# SwitchBoard_v4.net
KiCad netlist of a schematic drawn in Altium Designer
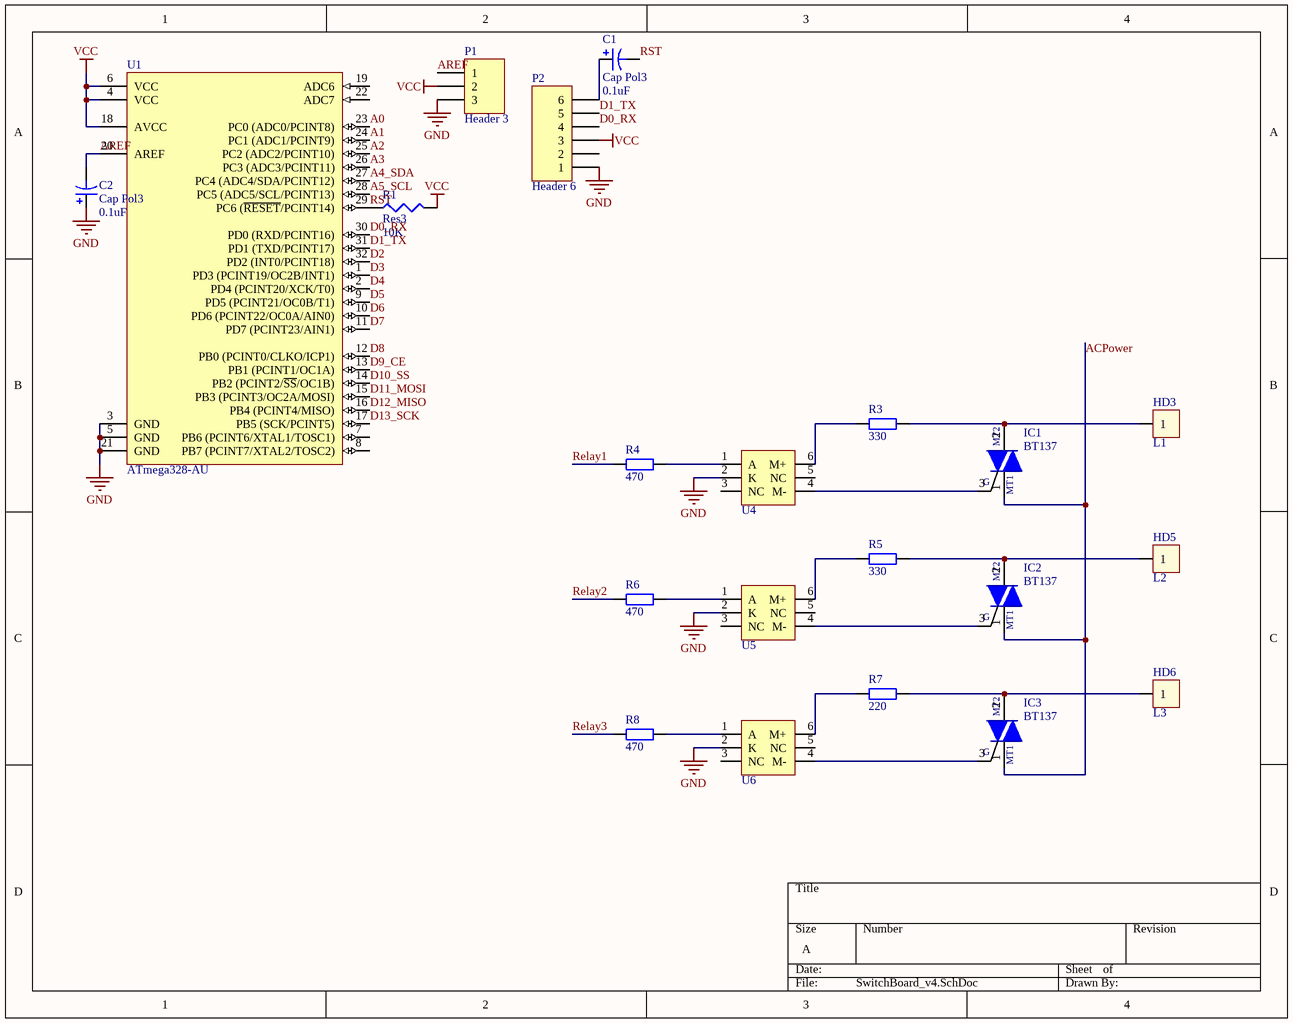
[diagram p0: SwitchBoard_v4.SchDoc]

(export (version "E")
  (design (tool "Eeschema 10.0.6"))
  (components
    (comp (ref "C1")
      (value "Cap Pol3")
      (footprint "C0805")
      (description "Polarized Capacitor (Surface Mount)")
      (fields (field (name "ALTIUM_VALUE") "0.1uF") (field (name "PUBLISHER") "Altium Limited"))
      (libsource (lib "Miscellaneous Devices") (part "Cap Pol3"))
    )
    (comp (ref "C2")
      (value "Cap Pol3")
      (footprint "C0805")
      (description "Polarized Capacitor (Surface Mount)")
      (fields (field (name "ALTIUM_VALUE") "0.1uF") (field (name "PUBLISHER") "Altium Limited"))
      (libsource (lib "Miscellaneous Devices") (part "Cap Pol3"))
    )
    (comp (ref "HD3")
      (value "L1")
      (footprint "DOMINO1")
      (description "Header 2 (Green)")
      (libsource (lib "myLibs") (part "Domino1"))
    )
    (comp (ref "HD5")
      (value "L2")
      (footprint "DOMINO1")
      (description "Header 2 (Green)")
      (libsource (lib "myLibs") (part "Domino1"))
    )
    (comp (ref "HD6")
      (value "L3")
      (footprint "DOMINO1")
      (description "Header 2 (Green)")
      (libsource (lib "myLibs") (part "Domino1"))
    )
    (comp (ref "IC1")
      (value "BT137")
      (footprint "QTO-220")
      (description "Triacs - 8A")
      (libsource (lib "myLibs") (part "BT137"))
    )
    (comp (ref "IC2")
      (value "BT137")
      (footprint "QTO-220")
      (description "Triacs - 8A")
      (libsource (lib "myLibs") (part "BT137"))
    )
    (comp (ref "IC3")
      (value "BT137")
      (footprint "QTO-220")
      (description "Triacs - 8A")
      (libsource (lib "myLibs") (part "BT137"))
    )
    (comp (ref "P1")
      (value "Header 3")
      (footprint "HDR1X3")
      (description "Header, 3-Pin")
      (fields (field (name "PUBLISHER") "Altium Limited"))
      (libsource (lib "Miscellaneous Connectors") (part "Header 3"))
    )
    (comp (ref "P2")
      (value "Header 6")
      (footprint "HDR1X6")
      (description "Header, 6-Pin")
      (fields (field (name "PUBLISHER") "Altium Limited"))
      (libsource (lib "Miscellaneous Connectors") (part "Header 6"))
    )
    (comp (ref "R1")
      (value "Res3")
      (footprint "J1-0603")
      (description "Resistor")
      (fields (field (name "ALTIUM_VALUE") "10K") (field (name "PUBLISHER") "Altium Limited"))
      (libsource (lib "Miscellaneous Devices") (part "Res3"))
    )
    (comp (ref "R3")
      (value "330")
      (footprint "R1/4W")
      (description "Resistor 1/4W")
      (libsource (lib "myLibs") (part "R1/4W"))
    )
    (comp (ref "R4")
      (value "470")
      (footprint "R1/4W")
      (description "Resistor 1/4W")
      (libsource (lib "myLibs") (part "R1/4W"))
    )
    (comp (ref "R5")
      (value "330")
      (footprint "R1/4W")
      (description "Resistor 1/4W")
      (libsource (lib "myLibs") (part "R1/4W"))
    )
    (comp (ref "R6")
      (value "470")
      (footprint "R1/4W")
      (description "Resistor 1/4W")
      (libsource (lib "myLibs") (part "R1/4W"))
    )
    (comp (ref "R7")
      (value "220")
      (footprint "R1/4W")
      (description "Resistor 1/4W")
      (libsource (lib "myLibs") (part "R1/4W"))
    )
    (comp (ref "R8")
      (value "470")
      (footprint "R1/4W")
      (description "Resistor 1/4W")
      (libsource (lib "myLibs") (part "R1/4W"))
    )
    (comp (ref "U1")
      (value "ATmega328-AU")
      (footprint "32A_N")
      (fields (field (name "PUBLISHER") "Altium Limited"))
      (libsource (lib "Atmel Microcontroller 8-Bit megaAVR") (part "ATmega328-AU"))
    )
    (comp (ref "U4") (value "MOC3021M") (footprint "MOC30XX") (libsource (lib "myLibs") (part "MOC3021M")))
    (comp (ref "U5") (value "MOC3021M") (footprint "MOC30XX") (libsource (lib "myLibs") (part "MOC3021M")))
    (comp (ref "U6") (value "MOC3021M") (footprint "MOC30XX") (libsource (lib "myLibs") (part "MOC3021M")))
  )
  (nets
    (net (code "1") (name "/A0") (class "Default")
      (node (ref "U1") (pin "23") (pinfunction "PC0_(ADC0/PCINT8)_23") (pintype "bidirectional"))
    )
    (net (code "2") (name "/A1") (class "Default")
      (node (ref "U1") (pin "24") (pinfunction "PC1_(ADC1/PCINT9)_24") (pintype "bidirectional"))
    )
    (net (code "3") (name "/A2") (class "Default")
      (node (ref "U1") (pin "25") (pinfunction "PC2_(ADC2/PCINT10)_25") (pintype "bidirectional"))
    )
    (net (code "4") (name "/A3") (class "Default")
      (node (ref "U1") (pin "26") (pinfunction "PC3_(ADC3/PCINT11)_26") (pintype "bidirectional"))
    )
    (net (code "5") (name "/A4_SDA") (class "Default")
      (node (ref "U1") (pin "27") (pinfunction "PC4_(ADC4/SDA/PCINT12)_27") (pintype "bidirectional"))
    )
    (net (code "6") (name "/A5_SCL") (class "Default")
      (node (ref "U1") (pin "28") (pinfunction "PC5_(ADC5/SCL/PCINT13)_28") (pintype "bidirectional"))
    )
    (net (code "7") (name "/ACPower") (class "Default")
      (node (ref "IC1") (pin "1") (pinfunction "MT1_1") (pintype "passive"))
      (node (ref "IC2") (pin "1") (pinfunction "MT1_1") (pintype "passive"))
      (node (ref "IC3") (pin "1") (pinfunction "MT1_1") (pintype "passive"))
    )
    (net (code "8") (name "/AREF") (class "Default")
      (node (ref "C2") (pin "2") (pinfunction "2_2") (pintype "passive"))
      (node (ref "P1") (pin "1") (pinfunction "1_1") (pintype "passive"))
      (node (ref "U1") (pin "20") (pinfunction "AREF_20") (pintype "passive"))
    )
    (net (code "9") (name "/D0_RX") (class "Default")
      (node (ref "P2") (pin "4") (pinfunction "4_4") (pintype "passive"))
      (node (ref "U1") (pin "30") (pinfunction "PD0_(RXD/PCINT16)_30") (pintype "bidirectional"))
    )
    (net (code "10") (name "/D1_TX") (class "Default")
      (node (ref "P2") (pin "5") (pinfunction "5_5") (pintype "passive"))
      (node (ref "U1") (pin "31") (pinfunction "PD1_(TXD/PCINT17)_31") (pintype "bidirectional"))
    )
    (net (code "11") (name "/D2") (class "Default")
      (node (ref "U1") (pin "32") (pinfunction "PD2_(INT0/PCINT18)_32") (pintype "bidirectional"))
    )
    (net (code "12") (name "/D3") (class "Default")
      (node (ref "U1") (pin "1") (pinfunction "PD3_(PCINT19/OC2B/INT1)_1") (pintype "bidirectional"))
    )
    (net (code "13") (name "/D4") (class "Default")
      (node (ref "U1") (pin "2") (pinfunction "PD4_(PCINT20/XCK/T0)_2") (pintype "bidirectional"))
    )
    (net (code "14") (name "/D5") (class "Default")
      (node (ref "U1") (pin "9") (pinfunction "PD5_(PCINT21/OC0B/T1)_9") (pintype "bidirectional"))
    )
    (net (code "15") (name "/D6") (class "Default")
      (node (ref "U1") (pin "10") (pinfunction "PD6_(PCINT22/OC0A/AIN0)_10") (pintype "bidirectional"))
    )
    (net (code "16") (name "/D7") (class "Default")
      (node (ref "U1") (pin "11") (pinfunction "PD7_(PCINT23/AIN1)_11") (pintype "bidirectional"))
    )
    (net (code "17") (name "/D8") (class "Default")
      (node (ref "U1") (pin "12") (pinfunction "PB0_(PCINT0/CLKO/ICP1)_12") (pintype "bidirectional"))
    )
    (net (code "18") (name "/D9_CE") (class "Default")
      (node (ref "U1") (pin "13") (pinfunction "PB1_(PCINT1/OC1A)_13") (pintype "bidirectional"))
    )
    (net (code "19") (name "/D10_SS") (class "Default")
      (node (ref "U1") (pin "14") (pinfunction "PB2_(PCINT2/~{SS}/OC1B)_14") (pintype "bidirectional"))
    )
    (net (code "20") (name "/D11_MOSI") (class "Default")
      (node (ref "U1") (pin "15") (pinfunction "PB3_(PCINT3/OC2A/MOSI)_15") (pintype "bidirectional"))
    )
    (net (code "21") (name "/D12_MISO") (class "Default")
      (node (ref "U1") (pin "16") (pinfunction "PB4_(PCINT4/MISO)_16") (pintype "bidirectional"))
    )
    (net (code "22") (name "/D13_SCK") (class "Default")
      (node (ref "U1") (pin "17") (pinfunction "PB5_(SCK/PCINT5)_17") (pintype "bidirectional"))
    )
    (net (code "23") (name "/RST") (class "Default")
      (node (ref "C1") (pin "2") (pinfunction "2_2") (pintype "passive"))
      (node (ref "R1") (pin "1") (pinfunction "1_1") (pintype "passive"))
      (node (ref "U1") (pin "29") (pinfunction "PC6_(~{RESET}/PCINT14)_29") (pintype "bidirectional"))
    )
    (net (code "24") (name "/Relay1") (class "Default")
      (node (ref "R4") (pin "1") (pinfunction "1_1") (pintype "passive"))
    )
    (net (code "25") (name "/Relay2") (class "Default")
      (node (ref "R6") (pin "1") (pinfunction "1_1") (pintype "passive"))
    )
    (net (code "26") (name "/Relay3") (class "Default")
      (node (ref "R8") (pin "1") (pinfunction "1_1") (pintype "passive"))
    )
    (net (code "27") (name "GND") (class "Default")
      (node (ref "C2") (pin "1") (pinfunction "1_1") (pintype "passive"))
      (node (ref "P1") (pin "3") (pinfunction "3_3") (pintype "passive"))
      (node (ref "P2") (pin "1") (pinfunction "1_1") (pintype "passive"))
      (node (ref "U1") (pin "21") (pinfunction "GND_21") (pintype "power_in"))
      (node (ref "U1") (pin "3") (pinfunction "GND_3") (pintype "power_in"))
      (node (ref "U1") (pin "5") (pinfunction "GND_5") (pintype "power_in"))
      (node (ref "U4") (pin "2") (pinfunction "K_2") (pintype "passive"))
      (node (ref "U5") (pin "2") (pinfunction "K_2") (pintype "passive"))
      (node (ref "U6") (pin "2") (pinfunction "K_2") (pintype "passive"))
    )
    (net (code "28") (name "Net-(C1-Pad1)") (class "Default")
      (node (ref "C1") (pin "1") (pinfunction "1_1") (pintype "passive"))
      (node (ref "P2") (pin "6") (pinfunction "6_6") (pintype "passive"))
    )
    (net (code "29") (name "Net-(IC1-IN)") (class "Default")
      (node (ref "IC1") (pin "3") (pinfunction "IN_3") (pintype "passive"))
      (node (ref "U4") (pin "4") (pinfunction "M-_4") (pintype "passive"))
    )
    (net (code "30") (name "Net-(IC1-MT2)") (class "Default")
      (node (ref "HD3") (pin "1") (pinfunction "1_1") (pintype "passive"))
      (node (ref "IC1") (pin "2") (pinfunction "MT2_2") (pintype "passive"))
      (node (ref "R3") (pin "2") (pinfunction "2_2") (pintype "passive"))
    )
    (net (code "31") (name "Net-(IC2-IN)") (class "Default")
      (node (ref "IC2") (pin "3") (pinfunction "IN_3") (pintype "passive"))
      (node (ref "U5") (pin "4") (pinfunction "M-_4") (pintype "passive"))
    )
    (net (code "32") (name "Net-(IC2-MT2)") (class "Default")
      (node (ref "HD5") (pin "1") (pinfunction "1_1") (pintype "passive"))
      (node (ref "IC2") (pin "2") (pinfunction "MT2_2") (pintype "passive"))
      (node (ref "R5") (pin "2") (pinfunction "2_2") (pintype "passive"))
    )
    (net (code "33") (name "Net-(IC3-IN)") (class "Default")
      (node (ref "IC3") (pin "3") (pinfunction "IN_3") (pintype "passive"))
      (node (ref "U6") (pin "4") (pinfunction "M-_4") (pintype "passive"))
    )
    (net (code "34") (name "Net-(IC3-MT2)") (class "Default")
      (node (ref "HD6") (pin "1") (pinfunction "1_1") (pintype "passive"))
      (node (ref "IC3") (pin "2") (pinfunction "MT2_2") (pintype "passive"))
      (node (ref "R7") (pin "2") (pinfunction "2_2") (pintype "passive"))
    )
    (net (code "35") (name "Net-(U4-A)") (class "Default")
      (node (ref "R4") (pin "2") (pinfunction "2_2") (pintype "passive"))
      (node (ref "U4") (pin "1") (pinfunction "A_1") (pintype "passive"))
    )
    (net (code "36") (name "Net-(U4-M+)") (class "Default")
      (node (ref "R3") (pin "1") (pinfunction "1_1") (pintype "passive"))
      (node (ref "U4") (pin "6") (pinfunction "M+_6") (pintype "passive"))
    )
    (net (code "37") (name "Net-(U5-A)") (class "Default")
      (node (ref "R6") (pin "2") (pinfunction "2_2") (pintype "passive"))
      (node (ref "U5") (pin "1") (pinfunction "A_1") (pintype "passive"))
    )
    (net (code "38") (name "Net-(U5-M+)") (class "Default")
      (node (ref "R5") (pin "1") (pinfunction "1_1") (pintype "passive"))
      (node (ref "U5") (pin "6") (pinfunction "M+_6") (pintype "passive"))
    )
    (net (code "39") (name "Net-(U6-A)") (class "Default")
      (node (ref "R8") (pin "2") (pinfunction "2_2") (pintype "passive"))
      (node (ref "U6") (pin "1") (pinfunction "A_1") (pintype "passive"))
    )
    (net (code "40") (name "Net-(U6-M+)") (class "Default")
      (node (ref "R7") (pin "1") (pinfunction "1_1") (pintype "passive"))
      (node (ref "U6") (pin "6") (pinfunction "M+_6") (pintype "passive"))
    )
    (net (code "41") (name "VCC") (class "Default")
      (node (ref "P1") (pin "2") (pinfunction "2_2") (pintype "passive"))
      (node (ref "P2") (pin "3") (pinfunction "3_3") (pintype "passive"))
      (node (ref "R1") (pin "2") (pinfunction "2_2") (pintype "passive"))
      (node (ref "U1") (pin "18") (pinfunction "AVCC_18") (pintype "power_in"))
      (node (ref "U1") (pin "4") (pinfunction "VCC_4") (pintype "power_in"))
      (node (ref "U1") (pin "6") (pinfunction "VCC_6") (pintype "power_in"))
    )
    (net (code "42") (name "unconnected-(P2-Pad2)") (class "Default")
      (node (ref "P2") (pin "2") (pinfunction "2_2") (pintype "passive"))
    )
    (net (code "43") (name "unconnected-(U1-ADC6-Pad19)") (class "Default")
      (node (ref "U1") (pin "19") (pinfunction "ADC6_19") (pintype "input"))
    )
    (net (code "44") (name "unconnected-(U1-ADC7-Pad22)") (class "Default")
      (node (ref "U1") (pin "22") (pinfunction "ADC7_22") (pintype "input"))
    )
    (net (code "45") (name "unconnected-(U1-PB6_(PCINT6{slash}XTAL1{slash}TOSC1)-Pad7)") (class "Default")
      (node (ref "U1") (pin "7") (pinfunction "PB6_(PCINT6/XTAL1/TOSC1)_7") (pintype "bidirectional"))
    )
    (net (code "46") (name "unconnected-(U1-PB7_(PCINT7{slash}XTAL2{slash}TOSC2)-Pad8)") (class "Default")
      (node (ref "U1") (pin "8") (pinfunction "PB7_(PCINT7/XTAL2/TOSC2)_8") (pintype "bidirectional"))
    )
    (net (code "47") (name "unconnected-(U4-NC-Pad3)") (class "Default")
      (node (ref "U4") (pin "3") (pinfunction "NC_3") (pintype "passive"))
    )
    (net (code "48") (name "unconnected-(U4-NC-Pad5)") (class "Default")
      (node (ref "U4") (pin "5") (pinfunction "NC_5") (pintype "passive"))
    )
    (net (code "49") (name "unconnected-(U5-NC-Pad3)") (class "Default")
      (node (ref "U5") (pin "3") (pinfunction "NC_3") (pintype "passive"))
    )
    (net (code "50") (name "unconnected-(U5-NC-Pad5)") (class "Default")
      (node (ref "U5") (pin "5") (pinfunction "NC_5") (pintype "passive"))
    )
    (net (code "51") (name "unconnected-(U6-NC-Pad3)") (class "Default")
      (node (ref "U6") (pin "3") (pinfunction "NC_3") (pintype "passive"))
    )
    (net (code "52") (name "unconnected-(U6-NC-Pad5)") (class "Default")
      (node (ref "U6") (pin "5") (pinfunction "NC_5") (pintype "passive"))
    )
  )
)
